# alu_slice.net
KiCad netlist of a schematic drawn in EAGLE
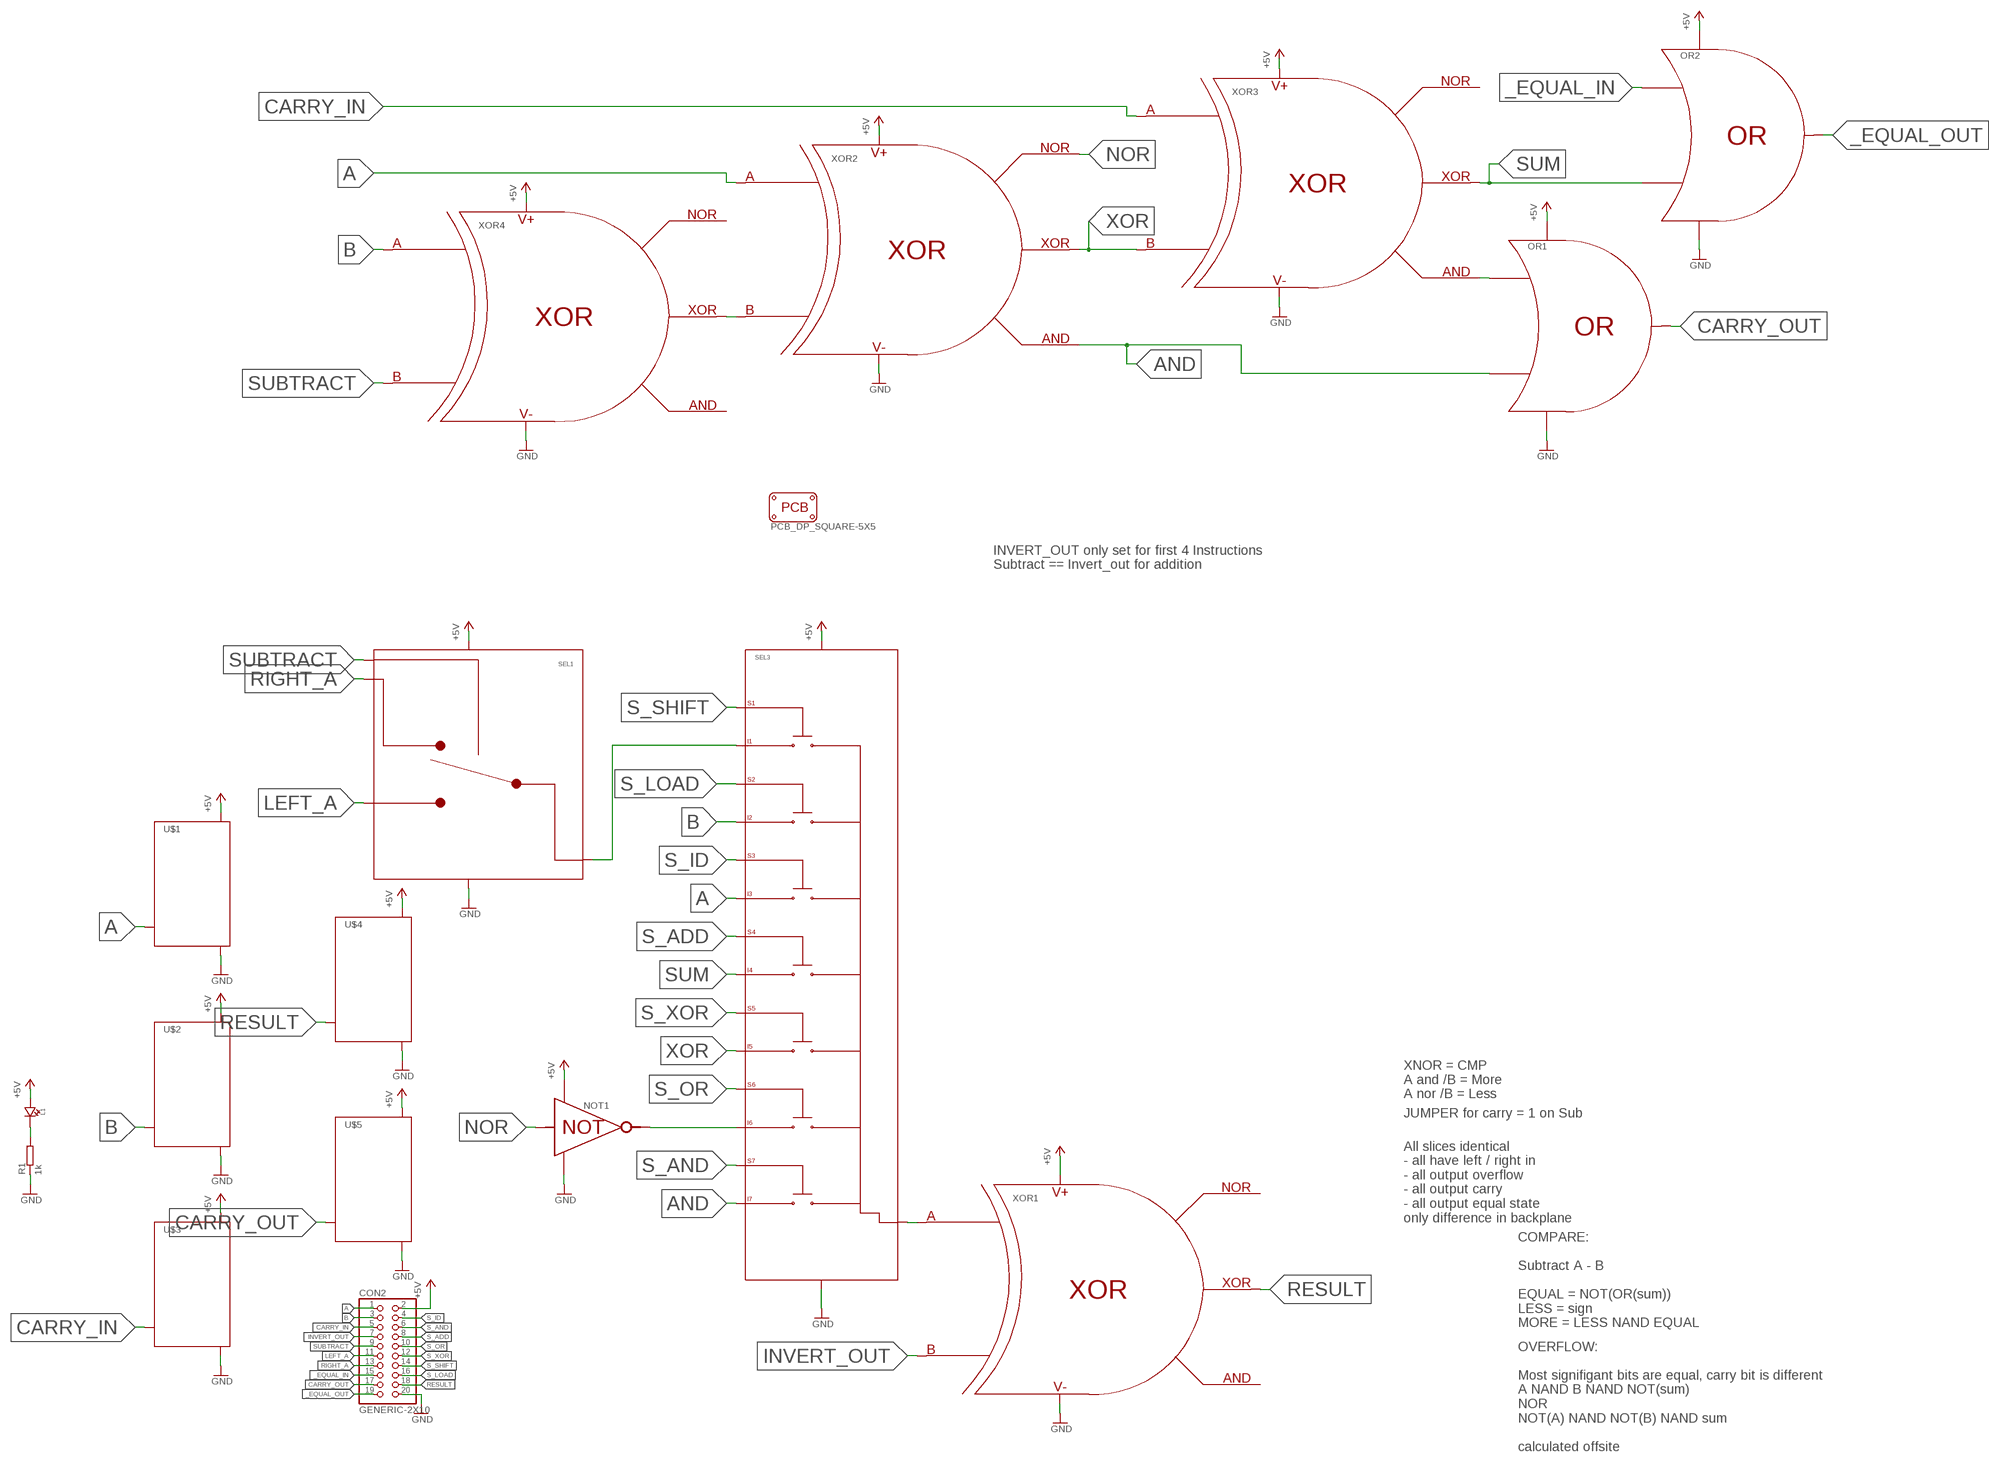
[diagram p0: schematic, sheet 1]

(export (version "E")
  (design (tool "Eeschema 10.0.6"))
  (components
    (comp (ref "CON2")
      (value "GENERIC-2X10")
      (footprint "eagle-import:PINHEADER-100MIL-2X10-EDGE")
      (libsource (lib "eagle-import") (part "GENERIC-2X10"))
    )
    (comp (ref "L1")
      (value "LED0805")
      (footprint "eagle-import:CHIPLED_0805")
      (libsource (lib "eagle-import") (part "LED0805"))
    )
    (comp (ref "NOT1")
      (value "NOTVERTICAL")
      (footprint "eagle-import:NOT-VERTICAL")
      (libsource (lib "eagle-import") (part "NOTVERTICAL"))
    )
    (comp (ref "OR1") (value "OR") (footprint "eagle-import:OR") (libsource (lib "eagle-import") (part "OR")))
    (comp (ref "OR2") (value "OR") (footprint "eagle-import:OR") (libsource (lib "eagle-import") (part "OR")))
    (comp (ref "PCB1")
      (value "PCB_DP_SQUARE-5X5")
      (footprint "eagle-import:DP5050_V1")
      (libsource (lib "eagle-import") (part "PCB_DP_SQUARE-5X5"))
    )
    (comp (ref "R1")
      (value "1k")
      (footprint "eagle-import:R0603-MARK")
      (libsource (lib "eagle-import") (part "R-EU-MARKEDR0603"))
    )
    (comp (ref "SEL1")
      (value "1_BIT_SELECT")
      (footprint "eagle-import:SELECTOR-2-LANE-NOMUX")
      (libsource (lib "eagle-import") (part "1_BIT_SELECT"))
    )
    (comp (ref "SEL3")
      (value "7_VAL_SELECT")
      (footprint "eagle-import:SELECTOR-7_BIT-NOMUX")
      (libsource (lib "eagle-import") (part "7_VAL_SELECT"))
    )
    (comp (ref "U$1")
      (value "LEDDRIVER")
      (footprint "eagle-import:LEDDRIVER")
      (libsource (lib "eagle-import") (part "LEDDRIVER"))
    )
    (comp (ref "U$2")
      (value "LEDDRIVER")
      (footprint "eagle-import:LEDDRIVER")
      (libsource (lib "eagle-import") (part "LEDDRIVER"))
    )
    (comp (ref "U$3")
      (value "LEDDRIVER")
      (footprint "eagle-import:LEDDRIVER")
      (libsource (lib "eagle-import") (part "LEDDRIVER"))
    )
    (comp (ref "U$4")
      (value "LEDDRIVER")
      (footprint "eagle-import:LEDDRIVER")
      (libsource (lib "eagle-import") (part "LEDDRIVER"))
    )
    (comp (ref "U$5")
      (value "LEDDRIVER")
      (footprint "eagle-import:LEDDRIVER")
      (libsource (lib "eagle-import") (part "LEDDRIVER"))
    )
    (comp (ref "XOR1")
      (value "XOR")
      (footprint "eagle-import:XOR")
      (libsource (lib "eagle-import") (part "XOR"))
    )
    (comp (ref "XOR2")
      (value "XOR")
      (footprint "eagle-import:XOR")
      (libsource (lib "eagle-import") (part "XOR"))
    )
    (comp (ref "XOR3")
      (value "XOR")
      (footprint "eagle-import:XOR")
      (libsource (lib "eagle-import") (part "XOR"))
    )
    (comp (ref "XOR4")
      (value "XOR")
      (footprint "eagle-import:XOR")
      (libsource (lib "eagle-import") (part "XOR"))
    )
  )
  (nets
    (net (code "1") (name "+5V") (class "Default")
      (node (ref "CON2") (pin "2") (pinfunction "2_2") (pintype "passive"))
      (node (ref "L1") (pin "A") (pinfunction "A_A") (pintype "bidirectional"))
      (node (ref "NOT1") (pin "_VP") (pinfunction "_VP__VP") (pintype "bidirectional"))
      (node (ref "OR1") (pin "_VP") (pinfunction "_VP__VP") (pintype "bidirectional"))
      (node (ref "OR2") (pin "_VP") (pinfunction "_VP__VP") (pintype "bidirectional"))
      (node (ref "SEL1") (pin "_VP") (pinfunction "_VP__VP") (pintype "bidirectional"))
      (node (ref "SEL3") (pin "_VP") (pinfunction "_VP__VP") (pintype "bidirectional"))
      (node (ref "U$1") (pin "_VP") (pinfunction "_VP__VP") (pintype "bidirectional"))
      (node (ref "U$2") (pin "_VP") (pinfunction "_VP__VP") (pintype "bidirectional"))
      (node (ref "U$3") (pin "_VP") (pinfunction "_VP__VP") (pintype "bidirectional"))
      (node (ref "U$4") (pin "_VP") (pinfunction "_VP__VP") (pintype "bidirectional"))
      (node (ref "U$5") (pin "_VP") (pinfunction "_VP__VP") (pintype "bidirectional"))
      (node (ref "XOR1") (pin "_VP") (pinfunction "_VP__VP") (pintype "bidirectional"))
      (node (ref "XOR2") (pin "_VP") (pinfunction "_VP__VP") (pintype "bidirectional"))
      (node (ref "XOR3") (pin "_VP") (pinfunction "_VP__VP") (pintype "bidirectional"))
      (node (ref "XOR4") (pin "_VP") (pinfunction "_VP__VP") (pintype "bidirectional"))
    )
    (net (code "2") (name "A") (class "Default")
      (node (ref "CON2") (pin "1") (pinfunction "1_1") (pintype "passive"))
      (node (ref "SEL3") (pin "I3") (pinfunction "I3_I3") (pintype "bidirectional"))
      (node (ref "U$1") (pin "A") (pinfunction "A_A") (pintype "bidirectional"))
      (node (ref "XOR2") (pin "A") (pinfunction "A_A") (pintype "bidirectional"))
    )
    (net (code "3") (name "AND") (class "Default")
      (node (ref "OR1") (pin "B") (pinfunction "B_B") (pintype "bidirectional"))
      (node (ref "SEL3") (pin "I7") (pinfunction "I7_I7") (pintype "bidirectional"))
      (node (ref "XOR2") (pin "AND") (pinfunction "AND_AND") (pintype "bidirectional"))
    )
    (net (code "4") (name "B") (class "Default")
      (node (ref "CON2") (pin "3") (pinfunction "3_3") (pintype "passive"))
      (node (ref "SEL3") (pin "I2") (pinfunction "I2_I2") (pintype "bidirectional"))
      (node (ref "U$2") (pin "A") (pinfunction "A_A") (pintype "bidirectional"))
      (node (ref "XOR4") (pin "A") (pinfunction "A_A") (pintype "bidirectional"))
    )
    (net (code "5") (name "CARRY_IN") (class "Default")
      (node (ref "CON2") (pin "5") (pinfunction "5_5") (pintype "passive"))
      (node (ref "U$3") (pin "A") (pinfunction "A_A") (pintype "bidirectional"))
      (node (ref "XOR3") (pin "A") (pinfunction "A_A") (pintype "bidirectional"))
    )
    (net (code "6") (name "CARRY_OUT") (class "Default")
      (node (ref "CON2") (pin "17") (pinfunction "17_17") (pintype "passive"))
      (node (ref "OR1") (pin "OR") (pinfunction "OR_OR") (pintype "bidirectional"))
      (node (ref "U$5") (pin "A") (pinfunction "A_A") (pintype "bidirectional"))
    )
    (net (code "7") (name "GND") (class "Default")
      (node (ref "CON2") (pin "20") (pinfunction "20_20") (pintype "passive"))
      (node (ref "NOT1") (pin "_VN") (pinfunction "_VN__VN") (pintype "bidirectional"))
      (node (ref "OR1") (pin "_VN") (pinfunction "_VN__VN") (pintype "bidirectional"))
      (node (ref "OR2") (pin "_VN") (pinfunction "_VN__VN") (pintype "bidirectional"))
      (node (ref "R1") (pin "1") (pinfunction "1_1") (pintype "passive"))
      (node (ref "SEL1") (pin "_VN") (pinfunction "_VN__VN") (pintype "bidirectional"))
      (node (ref "SEL3") (pin "_VN") (pinfunction "_VN__VN") (pintype "bidirectional"))
      (node (ref "U$1") (pin "_VN") (pinfunction "_VN__VN") (pintype "bidirectional"))
      (node (ref "U$2") (pin "_VN") (pinfunction "_VN__VN") (pintype "bidirectional"))
      (node (ref "U$3") (pin "_VN") (pinfunction "_VN__VN") (pintype "bidirectional"))
      (node (ref "U$4") (pin "_VN") (pinfunction "_VN__VN") (pintype "bidirectional"))
      (node (ref "U$5") (pin "_VN") (pinfunction "_VN__VN") (pintype "bidirectional"))
      (node (ref "XOR1") (pin "_VN") (pinfunction "_VN__VN") (pintype "bidirectional"))
      (node (ref "XOR2") (pin "_VN") (pinfunction "_VN__VN") (pintype "bidirectional"))
      (node (ref "XOR3") (pin "_VN") (pinfunction "_VN__VN") (pintype "bidirectional"))
      (node (ref "XOR4") (pin "_VN") (pinfunction "_VN__VN") (pintype "bidirectional"))
    )
    (net (code "8") (name "INVERT_OUT") (class "Default")
      (node (ref "CON2") (pin "7") (pinfunction "7_7") (pintype "passive"))
      (node (ref "XOR1") (pin "B") (pinfunction "B_B") (pintype "bidirectional"))
    )
    (net (code "9") (name "LEFT_A") (class "Default")
      (node (ref "CON2") (pin "11") (pinfunction "11_11") (pintype "passive"))
      (node (ref "SEL1") (pin "B") (pinfunction "B_B") (pintype "bidirectional"))
    )
    (net (code "10") (name "NOR") (class "Default")
      (node (ref "NOT1") (pin "A") (pinfunction "A_A") (pintype "bidirectional"))
      (node (ref "XOR2") (pin "NOR") (pinfunction "NOR_NOR") (pintype "bidirectional"))
    )
    (net (code "11") (name "Net-(L1-PadC)") (class "Default")
      (node (ref "L1") (pin "C") (pinfunction "C_C") (pintype "bidirectional"))
      (node (ref "R1") (pin "2") (pinfunction "2_2") (pintype "passive"))
    )
    (net (code "12") (name "Net-(NOT1-PadNOT)") (class "Default")
      (node (ref "NOT1") (pin "NOT") (pinfunction "NOT_NOT") (pintype "bidirectional"))
      (node (ref "SEL3") (pin "I6") (pinfunction "I6_I6") (pintype "bidirectional"))
    )
    (net (code "13") (name "Net-(OR1-PadA)") (class "Default")
      (node (ref "OR1") (pin "A") (pinfunction "A_A") (pintype "bidirectional"))
      (node (ref "XOR3") (pin "AND") (pinfunction "AND_AND") (pintype "bidirectional"))
    )
    (net (code "14") (name "Net-(SEL1-PadOUT)") (class "Default")
      (node (ref "SEL1") (pin "OUT") (pinfunction "OUT_OUT") (pintype "bidirectional"))
      (node (ref "SEL3") (pin "I1") (pinfunction "I1_I1") (pintype "bidirectional"))
    )
    (net (code "15") (name "Net-(SEL3-PadOUT)") (class "Default")
      (node (ref "SEL3") (pin "OUT") (pinfunction "OUT_OUT") (pintype "bidirectional"))
      (node (ref "XOR1") (pin "A") (pinfunction "A_A") (pintype "bidirectional"))
    )
    (net (code "16") (name "Net-(XOR2-PadB)") (class "Default")
      (node (ref "XOR2") (pin "B") (pinfunction "B_B") (pintype "bidirectional"))
      (node (ref "XOR4") (pin "XOR") (pinfunction "XOR_XOR") (pintype "bidirectional"))
    )
    (net (code "17") (name "RESULT") (class "Default")
      (node (ref "CON2") (pin "18") (pinfunction "18_18") (pintype "passive"))
      (node (ref "U$4") (pin "A") (pinfunction "A_A") (pintype "bidirectional"))
      (node (ref "XOR1") (pin "XOR") (pinfunction "XOR_XOR") (pintype "bidirectional"))
    )
    (net (code "18") (name "RIGHT_A") (class "Default")
      (node (ref "CON2") (pin "13") (pinfunction "13_13") (pintype "passive"))
      (node (ref "SEL1") (pin "A") (pinfunction "A_A") (pintype "bidirectional"))
    )
    (net (code "19") (name "SUBTRACT") (class "Default")
      (node (ref "CON2") (pin "9") (pinfunction "9_9") (pintype "passive"))
      (node (ref "SEL1") (pin "SEL") (pinfunction "SEL_SEL") (pintype "bidirectional"))
      (node (ref "XOR4") (pin "B") (pinfunction "B_B") (pintype "bidirectional"))
    )
    (net (code "20") (name "SUM") (class "Default")
      (node (ref "OR2") (pin "B") (pinfunction "B_B") (pintype "bidirectional"))
      (node (ref "SEL3") (pin "I4") (pinfunction "I4_I4") (pintype "bidirectional"))
      (node (ref "XOR3") (pin "XOR") (pinfunction "XOR_XOR") (pintype "bidirectional"))
    )
    (net (code "21") (name "S_ADD") (class "Default")
      (node (ref "CON2") (pin "8") (pinfunction "8_8") (pintype "passive"))
      (node (ref "SEL3") (pin "S4") (pinfunction "S4_S4") (pintype "bidirectional"))
    )
    (net (code "22") (name "S_AND") (class "Default")
      (node (ref "CON2") (pin "6") (pinfunction "6_6") (pintype "passive"))
      (node (ref "SEL3") (pin "S7") (pinfunction "S7_S7") (pintype "bidirectional"))
    )
    (net (code "23") (name "S_ID") (class "Default")
      (node (ref "CON2") (pin "4") (pinfunction "4_4") (pintype "passive"))
      (node (ref "SEL3") (pin "S3") (pinfunction "S3_S3") (pintype "bidirectional"))
    )
    (net (code "24") (name "S_LOAD") (class "Default")
      (node (ref "CON2") (pin "16") (pinfunction "16_16") (pintype "passive"))
      (node (ref "SEL3") (pin "S2") (pinfunction "S2_S2") (pintype "bidirectional"))
    )
    (net (code "25") (name "S_OR") (class "Default")
      (node (ref "CON2") (pin "10") (pinfunction "10_10") (pintype "passive"))
      (node (ref "SEL3") (pin "S6") (pinfunction "S6_S6") (pintype "bidirectional"))
    )
    (net (code "26") (name "S_SHIFT") (class "Default")
      (node (ref "CON2") (pin "14") (pinfunction "14_14") (pintype "passive"))
      (node (ref "SEL3") (pin "S1") (pinfunction "S1_S1") (pintype "bidirectional"))
    )
    (net (code "27") (name "S_XOR") (class "Default")
      (node (ref "CON2") (pin "12") (pinfunction "12_12") (pintype "passive"))
      (node (ref "SEL3") (pin "S5") (pinfunction "S5_S5") (pintype "bidirectional"))
    )
    (net (code "28") (name "XOR") (class "Default")
      (node (ref "SEL3") (pin "I5") (pinfunction "I5_I5") (pintype "bidirectional"))
      (node (ref "XOR2") (pin "XOR") (pinfunction "XOR_XOR") (pintype "bidirectional"))
      (node (ref "XOR3") (pin "B") (pinfunction "B_B") (pintype "bidirectional"))
    )
    (net (code "29") (name "_EQUAL_IN") (class "Default")
      (node (ref "CON2") (pin "15") (pinfunction "15_15") (pintype "passive"))
      (node (ref "OR2") (pin "A") (pinfunction "A_A") (pintype "bidirectional"))
    )
    (net (code "30") (name "_EQUAL_OUT") (class "Default")
      (node (ref "CON2") (pin "19") (pinfunction "19_19") (pintype "passive"))
      (node (ref "OR2") (pin "OR") (pinfunction "OR_OR") (pintype "bidirectional"))
    )
    (net (code "31") (name "unconnected-(XOR1-PadAND)") (class "Default")
      (node (ref "XOR1") (pin "AND") (pinfunction "AND_AND") (pintype "bidirectional"))
    )
    (net (code "32") (name "unconnected-(XOR1-PadNOR)") (class "Default")
      (node (ref "XOR1") (pin "NOR") (pinfunction "NOR_NOR") (pintype "bidirectional"))
    )
    (net (code "33") (name "unconnected-(XOR3-PadNOR)") (class "Default")
      (node (ref "XOR3") (pin "NOR") (pinfunction "NOR_NOR") (pintype "bidirectional"))
    )
    (net (code "34") (name "unconnected-(XOR4-PadAND)") (class "Default")
      (node (ref "XOR4") (pin "AND") (pinfunction "AND_AND") (pintype "bidirectional"))
    )
    (net (code "35") (name "unconnected-(XOR4-PadNOR)") (class "Default")
      (node (ref "XOR4") (pin "NOR") (pinfunction "NOR_NOR") (pintype "bidirectional"))
    )
  )
)
